# powersupply.net
KiCad netlist of a schematic drawn in Altium Designer
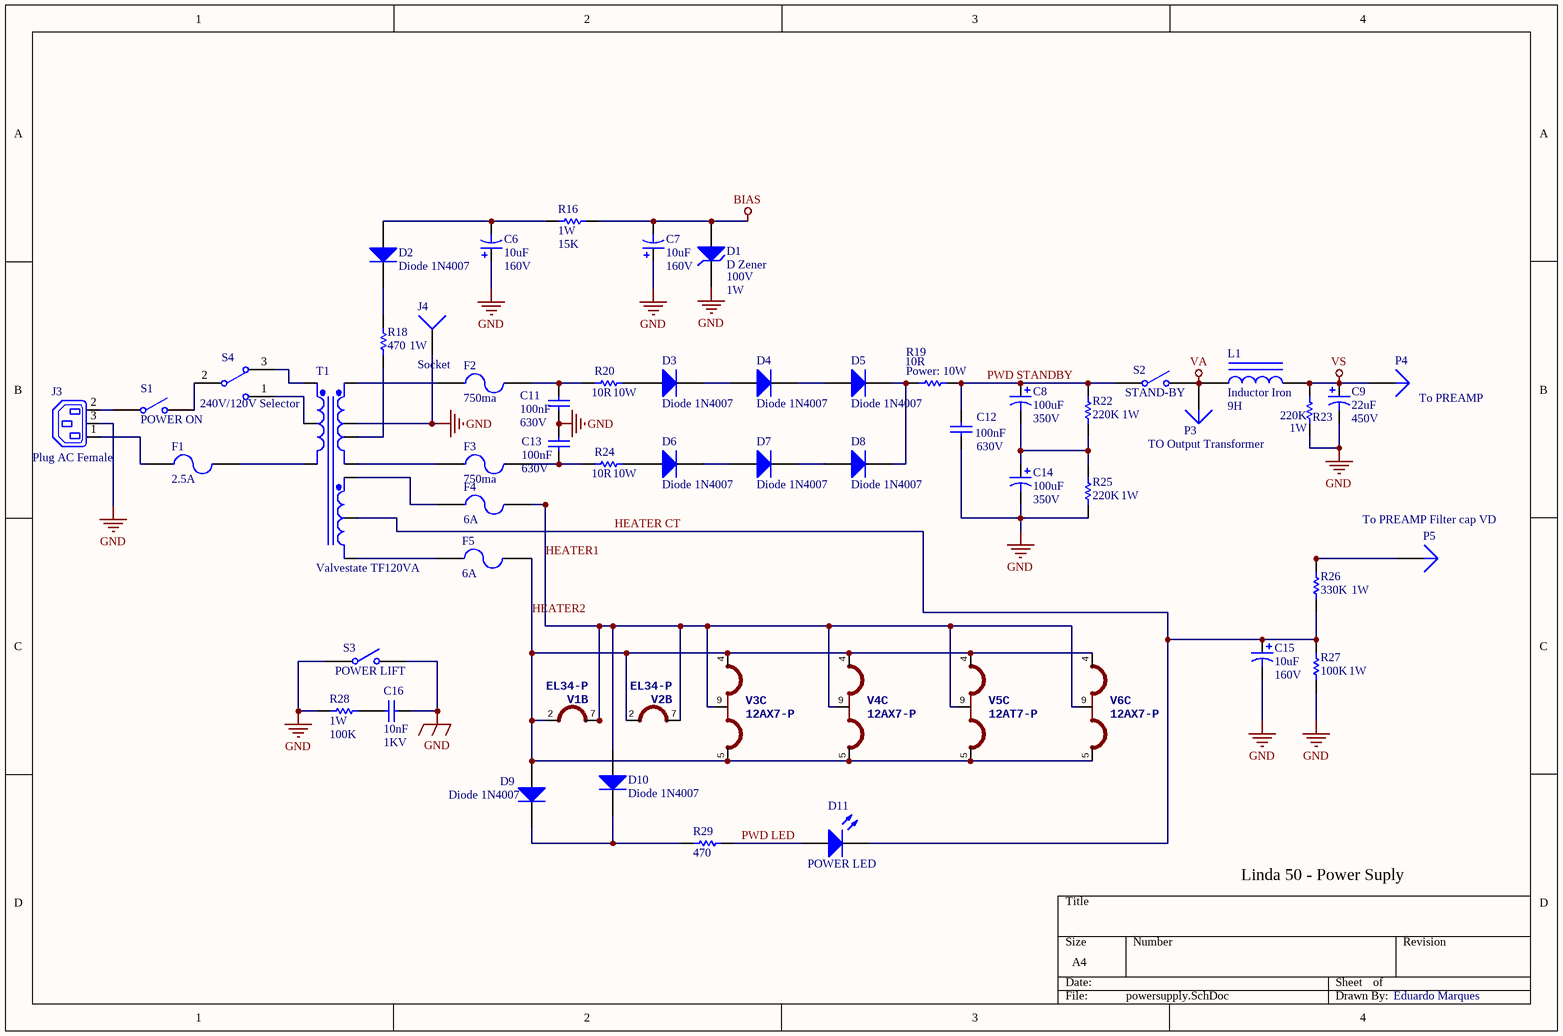
[diagram p0: powersupply.SchDoc]

(export (version "E")
  (design (tool "Eeschema 10.0.6"))
  (components
    (comp (ref "C6")
      (value "10uF")
      (footprint "RAD-POL-16x20x7.5")
      (description "Vishay 22uF 100V Polarized Capacitor (Radial); 2 Leads")
      (fields
        (field (name "PART NUMBER") "142 RHS")
        (field (name "VOLTAGE") "160V")
        (field (name "Comment") "Cap Pol Radial Vishay 22uF 100V")
        (field (name "PUBLISHER") "Altium Limited")
      )
      (libsource (lib "capacitors") (part "Cap Pol Radial Vishay 22uF 100V"))
    )
    (comp (ref "C7")
      (value "10uF")
      (footprint "RAD-POL-16x20x7.5")
      (description "Vishay 22uF 100V Polarized Capacitor (Radial); 2 Leads")
      (fields
        (field (name "PART NUMBER") "142 RHS")
        (field (name "VOLTAGE") "160V")
        (field (name "Comment") "Cap Pol Radial Vishay 22uF 100V")
        (field (name "PUBLISHER") "Altium Limited")
      )
      (libsource (lib "capacitors") (part "Cap Pol Radial Vishay 22uF 100V"))
    )
    (comp (ref "C8")
      (value "100uF")
      (footprint "FT Eletrolitic 100uF Axial")
      (description "FT Eletrolitic Polarized Capacitor Axial 100uF")
      (fields
        (field (name "VOLTAGE") "350V")
        (field (name "Comment") "Cap FT Eletrolitic 100uF Axial 350V")
        (field (name "PUBLISHER") "Whitesheep Amps")
      )
      (libsource (lib "capacitors") (part "Cap FT Eletrolitic 100uF Axial 350V"))
    )
    (comp (ref "C9")
      (value "22uF")
      (footprint "RAD-POL-7.6-15")
      (description "Polarized Capacitor (Axial)")
      (fields
        (field (name "VOLTAGE") "450V")
        (field (name "Comment") "Cap Pol Rad")
        (field (name "PUBLISHER") "Altium Limited")
      )
      (libsource (lib "capacitors") (part "Cap Pol Rad"))
    )
    (comp (ref "C11")
      (value "100nF")
      (footprint "CAP-XICON-100nF-630V")
      (description "Capacitor XICON (WINE COVER) Polypropilene CAP 630V")
      (fields
        (field (name "VOLTAGE") "630V")
        (field (name "Comment") "Orange Drop Capacitor")
        (field (name "PUBLISHER") "Altium Limited")
      )
      (libsource (lib "capacitors") (part "Cap-XICON-100nF-630V"))
    )
    (comp (ref "C12")
      (value "100nF")
      (footprint "CAP-XICON-100nF-630V")
      (description "Capacitor XICON (WINE COVER) Polypropilene CAP 630V")
      (fields
        (field (name "VOLTAGE") "630V")
        (field (name "Comment") "Orange Drop Capacitor")
        (field (name "PUBLISHER") "Altium Limited")
      )
      (libsource (lib "capacitors") (part "Cap-XICON-100nF-630V"))
    )
    (comp (ref "C13")
      (value "100nF")
      (footprint "CAP-XICON-100nF-630V")
      (description "Capacitor XICON (WINE COVER) Polypropilene CAP 630V")
      (fields
        (field (name "VOLTAGE") "630V")
        (field (name "Comment") "Orange Drop Capacitor")
        (field (name "PUBLISHER") "Altium Limited")
      )
      (libsource (lib "capacitors") (part "Cap-XICON-100nF-630V"))
    )
    (comp (ref "C14")
      (value "100uF")
      (footprint "FT Eletrolitic 100uF Axial")
      (description "FT Eletrolitic Polarized Capacitor Axial 100uF")
      (fields
        (field (name "VOLTAGE") "350V")
        (field (name "Comment") "Cap FT Eletrolitic 100uF Axial 350V")
        (field (name "PUBLISHER") "Whitesheep Amps")
      )
      (libsource (lib "capacitors") (part "Cap FT Eletrolitic 100uF Axial 350V"))
    )
    (comp (ref "C15")
      (value "10uF")
      (footprint "RAD-POL-16x20x7.5")
      (description "Vishay 22uF 100V Polarized Capacitor (Radial); 2 Leads")
      (fields
        (field (name "PART NUMBER") "142 RHS")
        (field (name "VOLTAGE") "160V")
        (field (name "Comment") "Cap Pol Radial Vishay 22uF 100V")
        (field (name "PUBLISHER") "Altium Limited")
      )
      (libsource (lib "capacitors") (part "Cap Pol Radial Vishay 22uF 100V"))
    )
    (comp (ref "C16")
      (value "10nF")
      (footprint "RAD-0.4")
      (description "Capacitor XICON (WINE COVER) Polypropilene CAP 630V")
      (fields
        (field (name "VOLTAGE") "1KV")
        (field (name "Comment") "Orange Drop Capacitor")
        (field (name "PUBLISHER") "Altium Limited")
      )
      (libsource (lib "capacitors") (part "Cap-XICON-100nF-630V"))
    )
    (comp (ref "D1")
      (value "D Zener")
      (footprint "ZENER 1W 100V")
      (description "Zener Diode")
      (fields
        (field (name "VOLTAGE") "100V")
        (field (name "POWER") "1W")
        (field (name "PUBLISHER") "Altium Limited")
      )
      (libsource (lib "Miscellaneous Devices") (part "D Zener"))
    )
    (comp (ref "D2")
      (value "Diode 1N4007")
      (footprint "1N4007-10.46mm Diode")
      (description "1 Amp General Purpose Rectifier")
      (fields (field (name "PUBLISHER") "Altium Limited"))
      (libsource (lib "Miscellaneous Devices") (part "Diode 1N4007"))
    )
    (comp (ref "D3")
      (value "Diode 1N4007")
      (footprint "1N4007-10.46mm Diode")
      (description "1 Amp General Purpose Rectifier")
      (fields (field (name "PUBLISHER") "Altium Limited"))
      (libsource (lib "diodes") (part "Diode 1N4007"))
    )
    (comp (ref "D4")
      (value "Diode 1N4007")
      (footprint "1N4007-10.46mm Diode")
      (description "1 Amp General Purpose Rectifier")
      (fields (field (name "PUBLISHER") "Altium Limited"))
      (libsource (lib "diodes") (part "Diode 1N4007"))
    )
    (comp (ref "D5")
      (value "Diode 1N4007")
      (footprint "1N4007-10.46mm Diode")
      (description "1 Amp General Purpose Rectifier")
      (fields (field (name "PUBLISHER") "Altium Limited"))
      (libsource (lib "diodes") (part "Diode 1N4007"))
    )
    (comp (ref "D6")
      (value "Diode 1N4007")
      (footprint "1N4007-10.46mm Diode")
      (description "1 Amp General Purpose Rectifier")
      (fields (field (name "PUBLISHER") "Altium Limited"))
      (libsource (lib "diodes") (part "Diode 1N4007"))
    )
    (comp (ref "D7")
      (value "Diode 1N4007")
      (footprint "1N4007-10.46mm Diode")
      (description "1 Amp General Purpose Rectifier")
      (fields (field (name "PUBLISHER") "Altium Limited"))
      (libsource (lib "diodes") (part "Diode 1N4007"))
    )
    (comp (ref "D8")
      (value "Diode 1N4007")
      (footprint "1N4007-10.46mm Diode")
      (description "1 Amp General Purpose Rectifier")
      (fields (field (name "PUBLISHER") "Altium Limited"))
      (libsource (lib "diodes") (part "Diode 1N4007"))
    )
    (comp (ref "D9")
      (value "Diode 1N4007")
      (footprint "1N4007-10.46mm Diode")
      (description "1 Amp General Purpose Rectifier")
      (fields (field (name "PUBLISHER") "Altium Limited"))
      (libsource (lib "diodes") (part "Diode 1N4007"))
    )
    (comp (ref "D10")
      (value "Diode 1N4007")
      (footprint "1N4007-10.46mm Diode")
      (description "1 Amp General Purpose Rectifier")
      (fields (field (name "PUBLISHER") "Altium Limited"))
      (libsource (lib "diodes") (part "Diode 1N4007"))
    )
    (comp (ref "D11")
      (value "POWER LED")
      (footprint "LED-1")
      (description "Typical RED GaAs LED")
      (fields (field (name "PUBLISHER") "Altium Limited"))
      (libsource (lib "Miscellaneous Devices") (part "LED1"))
    )
    (comp (ref "F1")
      (value "2.5A")
      (footprint "PIN-W2/E2.8")
      (description "Fuse")
      (fields (field (name "PUBLISHER") "Altium Limited"))
      (libsource (lib "Miscellaneous Devices") (part "Fuse 2"))
    )
    (comp (ref "F2")
      (value "750ma")
      (footprint "FUSE-PCB-6x31")
      (description "Fuse")
      (fields (field (name "PUBLISHER") "Altium Limited"))
      (libsource (lib "fuses") (part "Fuse 2"))
    )
    (comp (ref "F3")
      (value "750ma")
      (footprint "FUSE-PCB-6x31")
      (description "Fuse")
      (fields (field (name "PUBLISHER") "Altium Limited"))
      (libsource (lib "fuses") (part "Fuse 2"))
    )
    (comp (ref "F4")
      (value "6A")
      (footprint "FUSE-PCB-6x31")
      (description "Fuse")
      (fields (field (name "PUBLISHER") "Altium Limited"))
      (libsource (lib "fuses") (part "Fuse 2"))
    )
    (comp (ref "F5")
      (value "6A")
      (footprint "FUSE-PCB-6x31")
      (description "Fuse")
      (fields (field (name "PUBLISHER") "Altium Limited"))
      (libsource (lib "fuses") (part "Fuse 2"))
    )
    (comp (ref "J3")
      (value "Plug AC Female")
      (footprint "IEC7-2H3")
      (description "IEC Mains Power Outlet, EN60 320-2-2 F Class I, PC Flange Rear Mount, Chassis Socket")
      (fields (field (name "PUBLISHER") "Altium Limited"))
      (libsource (lib "Miscellaneous Connectors") (part "Plug AC Female"))
    )
    (comp (ref "J4")
      (value "Socket")
      (footprint "PIN1")
      (fields (field (name "PUBLISHER") "Altium Limited"))
      (libsource (lib "Miscellaneous Connectors") (part "Socket"))
    )
    (comp (ref "L1")
      (value "Inductor Iron")
      (footprint "AXIAL-0.9")
      (description "Magnetic-Core Inductor")
      (fields (field (name "ALTIUM_VALUE") "9H") (field (name "PUBLISHER") "Altium Limited"))
      (libsource (lib "Miscellaneous Devices") (part "Inductor Iron"))
    )
    (comp (ref "P3")
      (value "TO Output Transformer")
      (footprint "PIN1")
      (description "Plug")
      (fields (field (name "PUBLISHER") "Altium Limited"))
      (libsource (lib "Miscellaneous Connectors") (part "Plug"))
    )
    (comp (ref "P4")
      (value "To PREAMP")
      (footprint "PIN1")
      (description "Plug")
      (fields (field (name "PUBLISHER") "Altium Limited"))
      (libsource (lib "Miscellaneous Connectors") (part "Plug"))
    )
    (comp (ref "P5")
      (value "To PREAMP Filter cap VD")
      (footprint "PIN1")
      (description "Plug")
      (fields (field (name "PUBLISHER") "Altium Limited"))
      (libsource (lib "Miscellaneous Connectors") (part "Plug"))
    )
    (comp (ref "R16")
      (value "15K")
      (footprint "AXIAL-0.6")
      (description "Semiconductor Resistor")
      (fields
        (field (name "POWER") "1W")
        (field (name "Comment") "Metal Film Resistor 1W")
        (field (name "PUBLISHER") "Linda Hand Buit Amplifiers")
      )
      (libsource (lib "resistors") (part "Res Wire Wound 1W"))
    )
    (comp (ref "R18")
      (value "470")
      (footprint "AXIAL-0.6")
      (description "Semiconductor Resistor")
      (fields
        (field (name "POWER") "1W")
        (field (name "Comment") "Metal Film Resistor 1W")
        (field (name "PUBLISHER") "Linda Hand Buit Amplifiers")
      )
      (libsource (lib "resistors") (part "Res Wire Wound 1W"))
    )
    (comp (ref "R19")
      (value "10R")
      (footprint "Power Wirewound Resistor 10W - Vishay Dale")
      (description "Semiconductor Resistor")
      (fields
        (field (name "POWER") "10W")
        (field (name "MANUFACTURER PART NUMBER") "RS01010R00FE73")
        (field (name "Comment") "Wire Wound Power Resistor")
        (field (name "PUBLISHER") "Whitesheep Amps")
      )
      (libsource (lib "resistors") (part "Res Vishay Dale Wire Wound Power Resistor 10R 10W"))
    )
    (comp (ref "R20")
      (value "10R")
      (footprint "Power Wirewound Resistor 10W - Vishay Dale")
      (description "Semiconductor Resistor")
      (fields
        (field (name "POWER") "10W")
        (field (name "Comment") "Wire Wound Power Resistor")
        (field (name "PUBLISHER") "Whitesheep Amps")
      )
      (libsource (lib "resistors") (part "Res Wire Wound Power Resistor 5W"))
    )
    (comp (ref "R22")
      (value "220K")
      (footprint "RESISTOR-MetalOxide-3W")
      (description "Semiconductor Resistor")
      (fields
        (field (name "POWER") "1W")
        (field (name "Comment") "Metal Film Resistor 1W")
        (field (name "PUBLISHER") "Linda Hand Buit Amplifiers")
      )
      (libsource (lib "resistors") (part "Res Wire Wound 1W"))
    )
    (comp (ref "R23")
      (value "220K")
      (footprint "AXIAL-0.6")
      (description "Semiconductor Resistor")
      (fields
        (field (name "POWER") "1W")
        (field (name "Comment") "Metal Film Resistor 1W")
        (field (name "PUBLISHER") "Linda Hand Buit Amplifiers")
      )
      (libsource (lib "resistors") (part "Res Wire Wound 1W"))
    )
    (comp (ref "R24")
      (value "10R")
      (footprint "Power Wirewound Resistor 10W - Vishay Dale")
      (description "Semiconductor Resistor")
      (fields
        (field (name "POWER") "10W")
        (field (name "Comment") "Wire Wound Power Resistor")
        (field (name "PUBLISHER") "Whitesheep Amps")
      )
      (libsource (lib "resistors") (part "Res Wire Wound Power Resistor 5W"))
    )
    (comp (ref "R25")
      (value "220K")
      (footprint "RESISTOR-MetalOxide-3W")
      (description "Semiconductor Resistor")
      (fields
        (field (name "POWER") "1W")
        (field (name "Comment") "Metal Film Resistor 1W")
        (field (name "PUBLISHER") "Linda Hand Buit Amplifiers")
      )
      (libsource (lib "resistors") (part "Res Wire Wound 1W"))
    )
    (comp (ref "R26")
      (value "330K")
      (footprint "AXIAL-0.6")
      (description "Semiconductor Resistor")
      (fields
        (field (name "POWER") "1W")
        (field (name "Comment") "Metal Film Resistor 1W")
        (field (name "PUBLISHER") "Linda Hand Buit Amplifiers")
      )
      (libsource (lib "resistors") (part "Res Wire Wound 1W"))
    )
    (comp (ref "R27")
      (value "100K")
      (footprint "AXIAL-0.6")
      (description "Semiconductor Resistor")
      (fields
        (field (name "POWER") "1W")
        (field (name "Comment") "Metal Film Resistor 1W")
        (field (name "PUBLISHER") "Linda Hand Buit Amplifiers")
      )
      (libsource (lib "resistors") (part "Res Wire Wound 1W"))
    )
    (comp (ref "R28")
      (value "100K")
      (footprint "AXIAL-0.6")
      (description "Semiconductor Resistor")
      (fields
        (field (name "POWER") "1W")
        (field (name "Comment") "Metal Film Resistor 1W")
        (field (name "PUBLISHER") "Linda Hand Buit Amplifiers")
      )
      (libsource (lib "resistors") (part "Res Wire Wound 1W"))
    )
    (comp (ref "R29")
      (value "470")
      (footprint "AXIAL-0.6")
      (description "Semiconductor Resistor")
      (fields
        (field (name "POWER") "1/2W")
        (field (name "Comment") "Metal Film Resistor 1/2W")
        (field (name "PUBLISHER") "Whitesheep Amps")
      )
      (libsource (lib "resistors") (part "Res Metal Film 1/2W"))
    )
    (comp (ref "S1")
      (value "POWER ON")
      (footprint "SPST-2")
      (description "Single-Pole, Single-Throw Switch")
      (fields (field (name "PUBLISHER") "Altium Limited"))
      (libsource (lib "Miscellaneous Devices") (part "SW-SPST"))
    )
    (comp (ref "S2")
      (value "STAND-BY")
      (footprint "SPST-2")
      (description "Single-Pole, Single-Throw Switch")
      (fields (field (name "PUBLISHER") "Altium Limited"))
      (libsource (lib "Miscellaneous Devices") (part "SW-SPST"))
    )
    (comp (ref "S3")
      (value "POWER LIFT")
      (footprint "SPST-2")
      (description "Single-Pole, Single-Throw Switch")
      (fields (field (name "PUBLISHER") "Altium Limited"))
      (libsource (lib "Miscellaneous Devices") (part "SW-SPST"))
    )
    (comp (ref "S4")
      (value "240V/120V Selector")
      (footprint "SPDT")
      (description "SPDT Subminiature Toggle Switch, Right Angle Mounting, Vertical Actuation")
      (fields (field (name "PUBLISHER") "Altium Limited"))
      (libsource (lib "switches") (part "SW-SPDT"))
    )
    (comp (ref "T1")
      (value "Valvestate TF120VA")
      (footprint "TRF_5")
      (description "VALVESTATE TF 120VA")
      (fields (field (name "PUBLISHER") "LINDA Hand Built Amplifiers"))
      (libsource (lib "trafo") (part "Valvestate TF120VA"))
    )
    (comp (ref "V1") (value "EL34-P") (footprint "OKTAL") (libsource (lib "eagle_tubes_v6") (part "EL34-P")))
    (comp (ref "V2") (value "EL34-P") (footprint "OKTAL") (libsource (lib "eagle_tubes_v6") (part "EL34-P")))
    (comp (ref "V3")
      (value "12AX7-P")
      (footprint "NOVAL")
      (libsource (lib "eagle_tubes_v6") (part "12AX7-P"))
    )
    (comp (ref "V4")
      (value "12AX7-P")
      (footprint "NOVAL")
      (libsource (lib "eagle_tubes_v6") (part "12AX7-P"))
    )
    (comp (ref "V5")
      (value "12AT7-P")
      (footprint "NOVAL")
      (libsource (lib "eagle_tubes_v6") (part "12AT7-P"))
    )
    (comp (ref "V6")
      (value "12AX7-P")
      (footprint "NOVAL")
      (libsource (lib "eagle_tubes_v6") (part "12AX7-P"))
    )
  )
  (nets
    (net (code "1") (name "/HEATER CT") (class "Default")
      (node (ref "C15") (pin "1") (pinfunction "1_1") (pintype "passive"))
      (node (ref "D11") (pin "2") (pinfunction "K_2") (pintype "passive"))
      (node (ref "R26") (pin "1") (pinfunction "1_1") (pintype "passive"))
      (node (ref "R27") (pin "2") (pinfunction "2_2") (pintype "passive"))
      (node (ref "T1") (pin "9") (pinfunction "3.15V_CT_9") (pintype "passive"))
    )
    (net (code "2") (name "/HEATER1") (class "Default")
      (node (ref "D10") (pin "1") (pinfunction "A_1") (pintype "passive"))
      (node (ref "F4") (pin "2") (pinfunction "2_2") (pintype "passive"))
      (node (ref "V1") (pin "7") (pinfunction "H2_7") (pintype "passive"))
      (node (ref "V2") (pin "7") (pinfunction "H2_7") (pintype "passive"))
      (node (ref "V3") (pin "9") (pinfunction "H2_9") (pintype "passive"))
      (node (ref "V4") (pin "9") (pinfunction "H2_9") (pintype "passive"))
      (node (ref "V5") (pin "9") (pinfunction "H2_9") (pintype "passive"))
      (node (ref "V6") (pin "9") (pinfunction "H2_9") (pintype "passive"))
    )
    (net (code "3") (name "/HEATER2") (class "Default")
      (node (ref "D9") (pin "1") (pinfunction "A_1") (pintype "passive"))
      (node (ref "F5") (pin "2") (pinfunction "2_2") (pintype "passive"))
      (node (ref "V1") (pin "2") (pinfunction "H1_2") (pintype "passive"))
      (node (ref "V2") (pin "2") (pinfunction "H1_2") (pintype "passive"))
      (node (ref "V3") (pin "4") (pinfunction "H1_4") (pintype "passive"))
      (node (ref "V3") (pin "5") (pinfunction "H3_5") (pintype "passive"))
      (node (ref "V4") (pin "4") (pinfunction "H1_4") (pintype "passive"))
      (node (ref "V4") (pin "5") (pinfunction "H3_5") (pintype "passive"))
      (node (ref "V5") (pin "4") (pinfunction "H1_4") (pintype "passive"))
      (node (ref "V5") (pin "5") (pinfunction "H3_5") (pintype "passive"))
      (node (ref "V6") (pin "4") (pinfunction "H1_4") (pintype "passive"))
      (node (ref "V6") (pin "5") (pinfunction "H3_5") (pintype "passive"))
    )
    (net (code "4") (name "/PWD LED") (class "Default")
      (node (ref "D11") (pin "1") (pinfunction "A_1") (pintype "passive"))
      (node (ref "R29") (pin "2") (pinfunction "2_2") (pintype "passive"))
    )
    (net (code "5") (name "/PWD STANDBY") (class "Default")
      (node (ref "C12") (pin "2") (pinfunction "2_2") (pintype "passive"))
      (node (ref "C8") (pin "1") (pinfunction "1_1") (pintype "passive"))
      (node (ref "R19") (pin "2") (pinfunction "2_2") (pintype "passive"))
      (node (ref "R22") (pin "2") (pinfunction "2_2") (pintype "passive"))
      (node (ref "S2") (pin "1") (pinfunction "COMMON_1") (pintype "passive"))
    )
    (net (code "6") (name "BIAS") (class "Default")
      (node (ref "C7") (pin "2") (pinfunction "2_2") (pintype "passive"))
      (node (ref "D1") (pin "1") (pinfunction "A_1") (pintype "passive"))
      (node (ref "R16") (pin "1") (pinfunction "1_1") (pintype "passive"))
    )
    (net (code "7") (name "GND") (class "Default")
      (node (ref "C11") (pin "1") (pinfunction "1_1") (pintype "passive"))
      (node (ref "C12") (pin "1") (pinfunction "1_1") (pintype "passive"))
      (node (ref "C13") (pin "2") (pinfunction "2_2") (pintype "passive"))
      (node (ref "C14") (pin "2") (pinfunction "2_2") (pintype "passive"))
      (node (ref "C15") (pin "2") (pinfunction "2_2") (pintype "passive"))
      (node (ref "C16") (pin "1") (pinfunction "1_1") (pintype "passive"))
      (node (ref "C6") (pin "1") (pinfunction "1_1") (pintype "passive"))
      (node (ref "C7") (pin "1") (pinfunction "1_1") (pintype "passive"))
      (node (ref "C9") (pin "2") (pinfunction "2_2") (pintype "passive"))
      (node (ref "D1") (pin "2") (pinfunction "K_2") (pintype "passive"))
      (node (ref "J3") (pin "3") (pinfunction "E_3") (pintype "power_in"))
      (node (ref "J4") (pin "1") (pinfunction "1_1") (pintype "passive"))
      (node (ref "R23") (pin "1") (pinfunction "1_1") (pintype "passive"))
      (node (ref "R25") (pin "1") (pinfunction "1_1") (pintype "passive"))
      (node (ref "R27") (pin "1") (pinfunction "1_1") (pintype "passive"))
      (node (ref "R28") (pin "2") (pinfunction "2_2") (pintype "passive"))
      (node (ref "S3") (pin "1") (pinfunction "COMMON_1") (pintype "passive"))
      (node (ref "S3") (pin "2") (pinfunction "NO_2") (pintype "passive"))
      (node (ref "T1") (pin "5") (pinfunction "SEC_CT_5") (pintype "passive"))
    )
    (net (code "8") (name "Net-(C11-Pad2)") (class "Default")
      (node (ref "C11") (pin "2") (pinfunction "2_2") (pintype "passive"))
      (node (ref "F2") (pin "2") (pinfunction "2_2") (pintype "passive"))
      (node (ref "R20") (pin "1") (pinfunction "1_1") (pintype "passive"))
    )
    (net (code "9") (name "Net-(C13-Pad1)") (class "Default")
      (node (ref "C13") (pin "1") (pinfunction "1_1") (pintype "passive"))
      (node (ref "F3") (pin "2") (pinfunction "2_2") (pintype "passive"))
      (node (ref "R24") (pin "1") (pinfunction "1_1") (pintype "passive"))
    )
    (net (code "10") (name "Net-(C14-Pad1)") (class "Default")
      (node (ref "C14") (pin "1") (pinfunction "1_1") (pintype "passive"))
      (node (ref "C8") (pin "2") (pinfunction "2_2") (pintype "passive"))
      (node (ref "R22") (pin "1") (pinfunction "1_1") (pintype "passive"))
      (node (ref "R25") (pin "2") (pinfunction "2_2") (pintype "passive"))
    )
    (net (code "11") (name "Net-(C16-Pad2)") (class "Default")
      (node (ref "C16") (pin "2") (pinfunction "2_2") (pintype "passive"))
      (node (ref "R28") (pin "1") (pinfunction "1_1") (pintype "passive"))
    )
    (net (code "12") (name "Net-(D2-A)") (class "Default")
      (node (ref "C6") (pin "2") (pinfunction "2_2") (pintype "passive"))
      (node (ref "D2") (pin "1") (pinfunction "A_1") (pintype "passive"))
      (node (ref "R16") (pin "2") (pinfunction "2_2") (pintype "passive"))
    )
    (net (code "13") (name "Net-(D2-K)") (class "Default")
      (node (ref "D2") (pin "2") (pinfunction "K_2") (pintype "passive"))
      (node (ref "R18") (pin "2") (pinfunction "2_2") (pintype "passive"))
    )
    (net (code "14") (name "Net-(D3-A)") (class "Default")
      (node (ref "D3") (pin "1") (pinfunction "A_1") (pintype "passive"))
      (node (ref "R20") (pin "2") (pinfunction "2_2") (pintype "passive"))
    )
    (net (code "15") (name "Net-(D3-K)") (class "Default")
      (node (ref "D3") (pin "2") (pinfunction "K_2") (pintype "passive"))
      (node (ref "D4") (pin "1") (pinfunction "A_1") (pintype "passive"))
    )
    (net (code "16") (name "Net-(D4-K)") (class "Default")
      (node (ref "D4") (pin "2") (pinfunction "K_2") (pintype "passive"))
      (node (ref "D5") (pin "1") (pinfunction "A_1") (pintype "passive"))
    )
    (net (code "17") (name "Net-(D5-K)") (class "Default")
      (node (ref "D5") (pin "2") (pinfunction "K_2") (pintype "passive"))
      (node (ref "D8") (pin "2") (pinfunction "K_2") (pintype "passive"))
      (node (ref "R19") (pin "1") (pinfunction "1_1") (pintype "passive"))
    )
    (net (code "18") (name "Net-(D6-A)") (class "Default")
      (node (ref "D6") (pin "1") (pinfunction "A_1") (pintype "passive"))
      (node (ref "R24") (pin "2") (pinfunction "2_2") (pintype "passive"))
    )
    (net (code "19") (name "Net-(D6-K)") (class "Default")
      (node (ref "D6") (pin "2") (pinfunction "K_2") (pintype "passive"))
      (node (ref "D7") (pin "1") (pinfunction "A_1") (pintype "passive"))
    )
    (net (code "20") (name "Net-(D7-K)") (class "Default")
      (node (ref "D7") (pin "2") (pinfunction "K_2") (pintype "passive"))
      (node (ref "D8") (pin "1") (pinfunction "A_1") (pintype "passive"))
    )
    (net (code "21") (name "Net-(D10-K)") (class "Default")
      (node (ref "D10") (pin "2") (pinfunction "K_2") (pintype "passive"))
      (node (ref "D9") (pin "2") (pinfunction "K_2") (pintype "passive"))
      (node (ref "R29") (pin "1") (pinfunction "1_1") (pintype "passive"))
    )
    (net (code "22") (name "Net-(J3-L)") (class "Default")
      (node (ref "F1") (pin "1") (pinfunction "1_1") (pintype "passive"))
      (node (ref "J3") (pin "1") (pinfunction "L_1") (pintype "power_in"))
    )
    (net (code "23") (name "Net-(J3-N)") (class "Default")
      (node (ref "J3") (pin "2") (pinfunction "N_2") (pintype "power_in"))
      (node (ref "S1") (pin "1") (pinfunction "COMMON_1") (pintype "passive"))
    )
    (net (code "24") (name "Net-(P5-Pad1)") (class "Default")
      (node (ref "P5") (pin "1") (pinfunction "1_1") (pintype "passive"))
      (node (ref "R26") (pin "2") (pinfunction "2_2") (pintype "passive"))
    )
    (net (code "25") (name "Net-(S1-NO)") (class "Default")
      (node (ref "S1") (pin "2") (pinfunction "NO_2") (pintype "passive"))
      (node (ref "S4") (pin "2") (pinfunction "2_2") (pintype "passive"))
    )
    (net (code "26") (name "Net-(T1-3.15V+)") (class "Default")
      (node (ref "F4") (pin "1") (pinfunction "1_1") (pintype "passive"))
      (node (ref "T1") (pin "8") (pinfunction "3.15V+_8") (pintype "passive"))
    )
    (net (code "27") (name "Net-(T1-3.15V_-)") (class "Default")
      (node (ref "F5") (pin "1") (pinfunction "1_1") (pintype "passive"))
      (node (ref "T1") (pin "10") (pinfunction "3.15V_-_10") (pintype "passive"))
    )
    (net (code "28") (name "Net-(T1-Pri+220V)") (class "Default")
      (node (ref "S4") (pin "3") (pinfunction "3_3") (pintype "passive"))
      (node (ref "T1") (pin "1") (pinfunction "Pri+220V_1") (pintype "passive"))
    )
    (net (code "29") (name "Net-(T1-Pri+_127V)") (class "Default")
      (node (ref "S4") (pin "1") (pinfunction "1_1") (pintype "passive"))
      (node (ref "T1") (pin "2") (pinfunction "Pri+_127V_2") (pintype "passive"))
    )
    (net (code "30") (name "Net-(T1-Pri-)") (class "Default")
      (node (ref "F1") (pin "2") (pinfunction "2_2") (pintype "passive"))
      (node (ref "T1") (pin "3") (pinfunction "Pri-_3") (pintype "passive"))
    )
    (net (code "31") (name "Net-(T1-Sec_55V_+)") (class "Default")
      (node (ref "R18") (pin "1") (pinfunction "1_1") (pintype "passive"))
      (node (ref "T1") (pin "6") (pinfunction "Sec_55V_+_6") (pintype "passive"))
    )
    (net (code "32") (name "Net-(T1-Sec_355V_+)") (class "Default")
      (node (ref "F2") (pin "1") (pinfunction "1_1") (pintype "passive"))
      (node (ref "T1") (pin "4") (pinfunction "Sec_355V_+_4") (pintype "passive"))
    )
    (net (code "33") (name "Net-(T1-Sec_355V_-)") (class "Default")
      (node (ref "F3") (pin "1") (pinfunction "1_1") (pintype "passive"))
      (node (ref "T1") (pin "7") (pinfunction "Sec_355V_-_7") (pintype "passive"))
    )
    (net (code "34") (name "VA") (class "Default")
      (node (ref "L1") (pin "1") (pinfunction "1_1") (pintype "passive"))
      (node (ref "P3") (pin "1") (pinfunction "1_1") (pintype "passive"))
      (node (ref "S2") (pin "2") (pinfunction "NO_2") (pintype "passive"))
    )
    (net (code "35") (name "VS") (class "Default")
      (node (ref "C9") (pin "1") (pinfunction "1_1") (pintype "passive"))
      (node (ref "L1") (pin "2") (pinfunction "2_2") (pintype "passive"))
      (node (ref "P4") (pin "1") (pinfunction "1_1") (pintype "passive"))
      (node (ref "R23") (pin "2") (pinfunction "2_2") (pintype "passive"))
    )
  )
)
